# Sheet1.net
KiCad netlist of a schematic drawn in Altium Designer
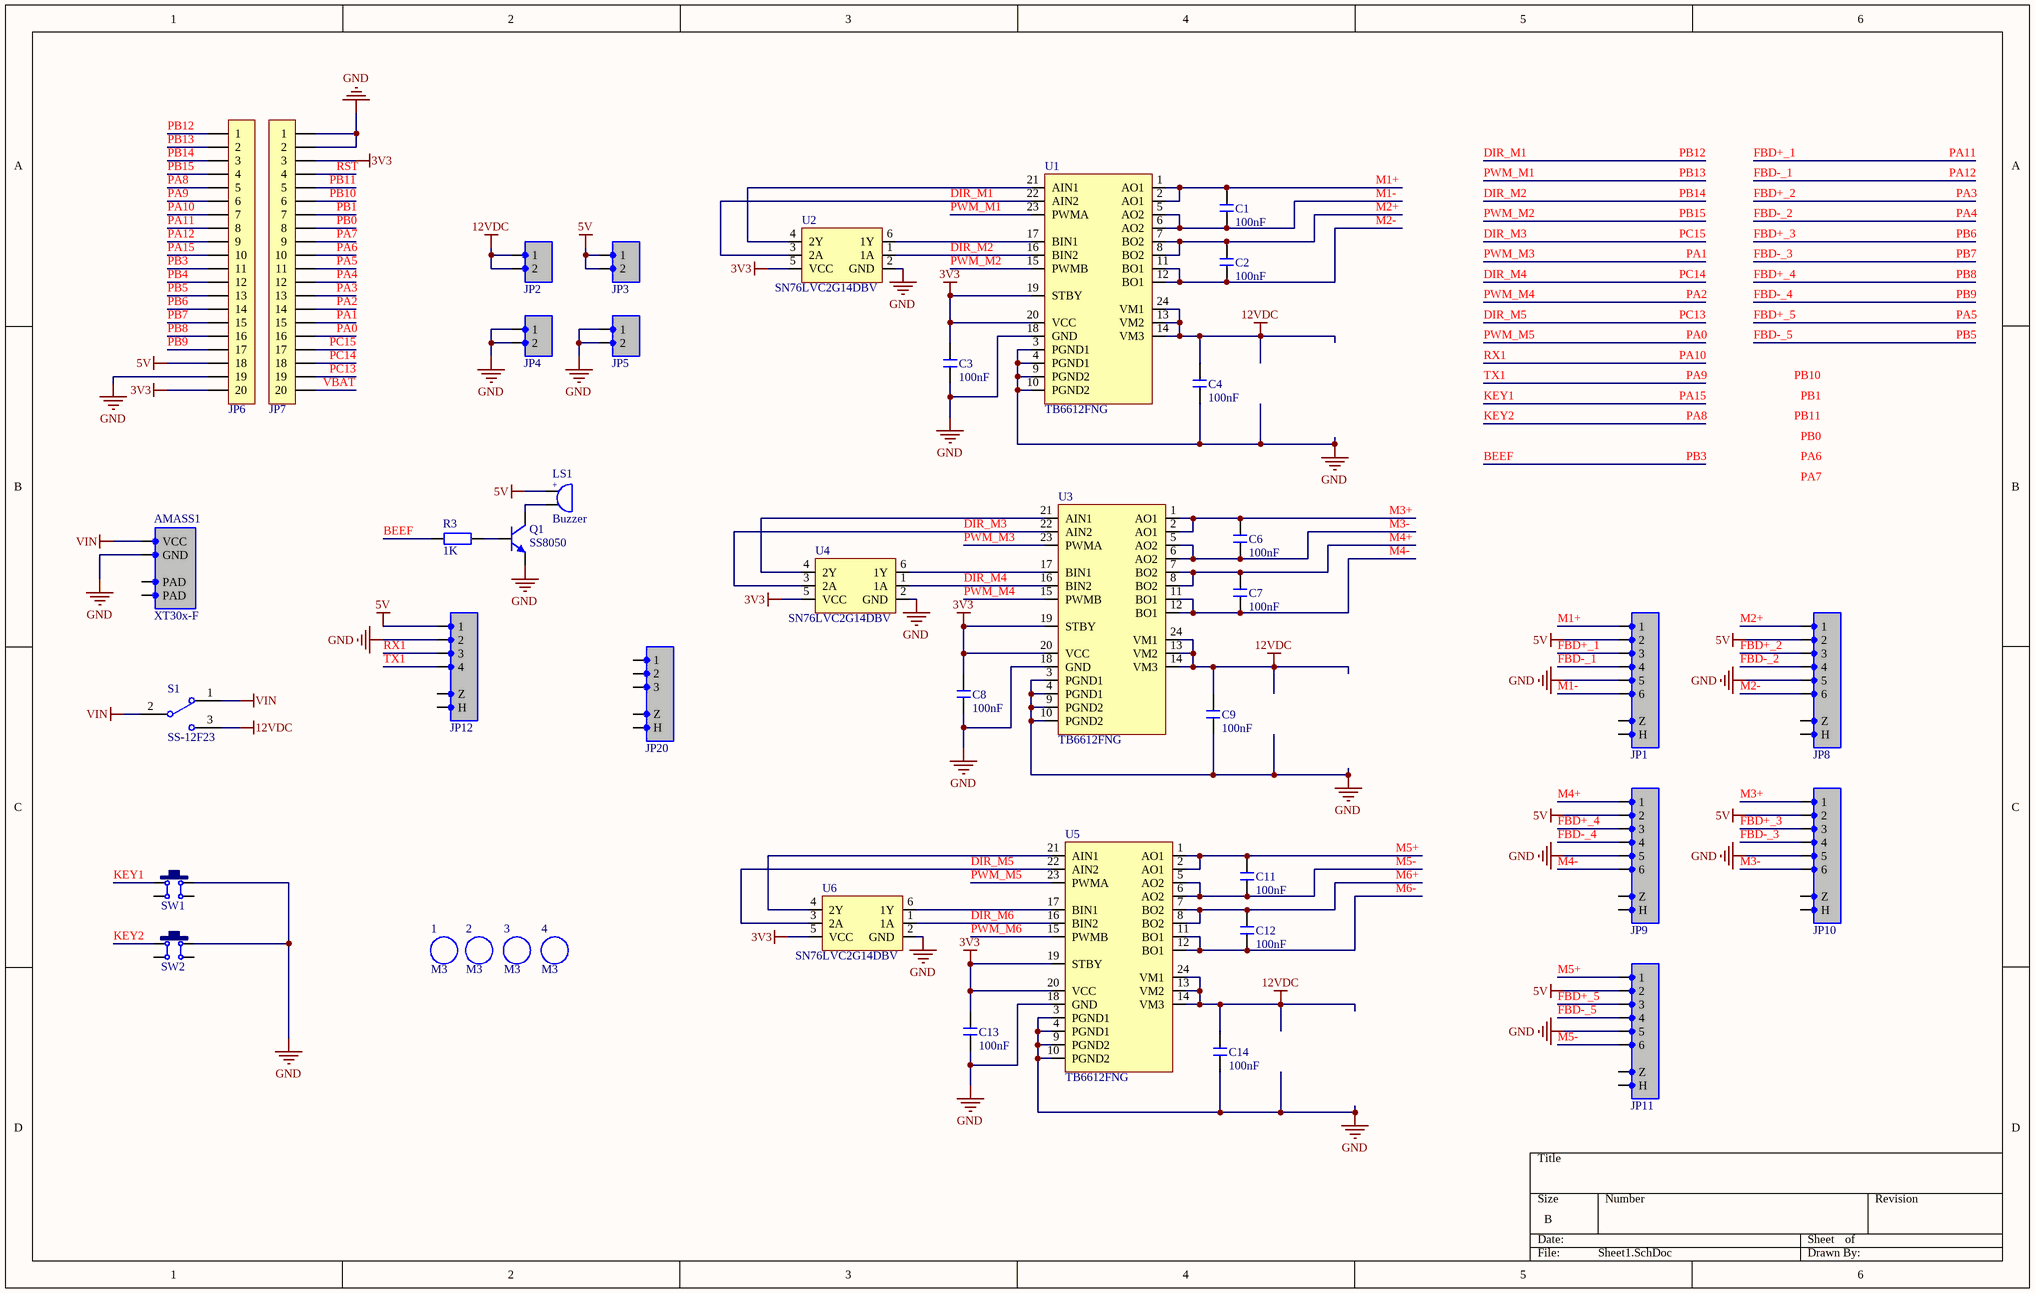
[diagram p0: Sheet1.SchDoc]

(export (version "E")
  (design (tool "Eeschema 10.0.6"))
  (components
    (comp (ref "1")
      (value "M3")
      (footprint "M3 125X200")
      (description "铜柱孔")
      (fields (field (name "版权归属") "源创客"))
      (libsource (lib "13.1-未分类器件") (part "M3"))
    )
    (comp (ref "2")
      (value "M3")
      (footprint "M3 125X200")
      (description "铜柱孔")
      (fields (field (name "版权归属") "源创客"))
      (libsource (lib "13.1-未分类器件") (part "M3"))
    )
    (comp (ref "3")
      (value "M3")
      (footprint "M3 125X200")
      (description "铜柱孔")
      (fields (field (name "版权归属") "源创客"))
      (libsource (lib "13.1-未分类器件") (part "M3"))
    )
    (comp (ref "4")
      (value "M3")
      (footprint "M3 125X200")
      (description "铜柱孔")
      (fields (field (name "版权归属") "源创客"))
      (libsource (lib "13.1-未分类器件") (part "M3"))
    )
    (comp (ref "AMASS1")
      (value "XT30x-F")
      (footprint "XT30U-M")
      (description "Amass防打火电源接口，XT30系列")
      (libsource (lib "SCHLib") (part "XT30"))
    )
    (comp (ref "C1")
      (value "100nF")
      (footprint "C 0603_L")
      (description "无极性贴片电容")
      (fields (field (name "版权归属") "源创客"))
      (libsource (lib "3.2-电容") (part "C"))
    )
    (comp (ref "C2")
      (value "100nF")
      (footprint "C 0603_L")
      (description "无极性贴片电容")
      (fields (field (name "版权归属") "源创客"))
      (libsource (lib "3.2-电容") (part "C"))
    )
    (comp (ref "C3")
      (value "100nF")
      (footprint "C 0603_L")
      (description "无极性贴片电容")
      (fields (field (name "版权归属") "源创客"))
      (libsource (lib "3.2-电容") (part "C"))
    )
    (comp (ref "C4")
      (value "100nF")
      (footprint "C 1206_L")
      (description "无极性贴片电容")
      (fields (field (name "版权归属") "源创客"))
      (libsource (lib "3.2-电容") (part "C"))
    )
    (comp (ref "C6")
      (value "100nF")
      (footprint "C 0603_L")
      (description "无极性贴片电容")
      (fields (field (name "版权归属") "源创客"))
      (libsource (lib "3.2-电容") (part "C"))
    )
    (comp (ref "C7")
      (value "100nF")
      (footprint "C 0603_L")
      (description "无极性贴片电容")
      (fields (field (name "版权归属") "源创客"))
      (libsource (lib "3.2-电容") (part "C"))
    )
    (comp (ref "C8")
      (value "100nF")
      (footprint "C 0603_L")
      (description "无极性贴片电容")
      (fields (field (name "版权归属") "源创客"))
      (libsource (lib "3.2-电容") (part "C"))
    )
    (comp (ref "C9")
      (value "100nF")
      (footprint "C 1206_L")
      (description "无极性贴片电容")
      (fields (field (name "版权归属") "源创客"))
      (libsource (lib "3.2-电容") (part "C"))
    )
    (comp (ref "C11")
      (value "100nF")
      (footprint "C 0603_L")
      (description "无极性贴片电容")
      (fields (field (name "版权归属") "源创客"))
      (libsource (lib "3.2-电容") (part "C"))
    )
    (comp (ref "C12")
      (value "100nF")
      (footprint "C 0603_L")
      (description "无极性贴片电容")
      (fields (field (name "版权归属") "源创客"))
      (libsource (lib "3.2-电容") (part "C"))
    )
    (comp (ref "C13")
      (value "100nF")
      (footprint "C 0603_L")
      (description "无极性贴片电容")
      (fields (field (name "版权归属") "源创客"))
      (libsource (lib "3.2-电容") (part "C"))
    )
    (comp (ref "C14")
      (value "100nF")
      (footprint "C 1206_L")
      (description "无极性贴片电容")
      (fields (field (name "版权归属") "源创客"))
      (libsource (lib "3.2-电容") (part "C"))
    )
    (comp (ref "JP1")
      (value "HDR-1X6")
      (footprint "XH2.54-WI-6P")
      (description "6P接插件")
      (fields (field (name "版权归属") "源创客"))
      (libsource (lib "14.6-接插件-脚距2.54") (part "Header 6"))
    )
    (comp (ref "JP2")
      (value "HDR-1X2")
      (footprint "HDR2.54-LI-2P")
      (description "2P接插件")
      (fields (field (name "版权归属") "源创客"))
      (libsource (lib "14.6-接插件-脚距2.54") (part "Header 2"))
    )
    (comp (ref "JP3")
      (value "HDR-1X2")
      (footprint "HDR2.54-LI-2P")
      (description "2P接插件")
      (fields (field (name "版权归属") "源创客"))
      (libsource (lib "14.6-接插件-脚距2.54") (part "Header 2"))
    )
    (comp (ref "JP4")
      (value "HDR-1X2")
      (footprint "HDR2.54-LI-2P")
      (description "2P接插件")
      (fields (field (name "版权归属") "源创客"))
      (libsource (lib "14.6-接插件-脚距2.54") (part "Header 2"))
    )
    (comp (ref "JP5")
      (value "HDR-1X2")
      (footprint "HDR2.54-LI-2P")
      (description "2P接插件")
      (fields (field (name "版权归属") "源创客"))
      (libsource (lib "14.6-接插件-脚距2.54") (part "Header 2"))
    )
    (comp (ref "JP6")
      (value "HDR-1X20")
      (footprint "HDR2.54-LI-20P")
      (description "20P接插件")
      (fields (field (name "版权归属") "源创客"))
      (libsource (lib "14.6-接插件-脚距2.54") (part "Header 20"))
    )
    (comp (ref "JP7")
      (value "HDR-1X20")
      (footprint "HDR2.54-LI-20P")
      (description "20P接插件")
      (fields (field (name "版权归属") "源创客"))
      (libsource (lib "") (part "Header 20_1"))
    )
    (comp (ref "JP8")
      (value "HDR-1X6")
      (footprint "XH2.54-WI-6P")
      (description "6P接插件")
      (fields (field (name "版权归属") "源创客"))
      (libsource (lib "14.6-接插件-脚距2.54") (part "Header 6"))
    )
    (comp (ref "JP9")
      (value "HDR-1X6")
      (footprint "XH2.54-WI-6P")
      (description "6P接插件")
      (fields (field (name "版权归属") "源创客"))
      (libsource (lib "14.6-接插件-脚距2.54") (part "Header 6"))
    )
    (comp (ref "JP10")
      (value "HDR-1X6")
      (footprint "XH2.54-WI-6P")
      (description "6P接插件")
      (fields (field (name "版权归属") "源创客"))
      (libsource (lib "14.6-接插件-脚距2.54") (part "Header 6"))
    )
    (comp (ref "JP11")
      (value "HDR-1X6")
      (footprint "XH2.54-WI-6P")
      (description "6P接插件")
      (fields (field (name "版权归属") "源创客"))
      (libsource (lib "14.6-接插件-脚距2.54") (part "Header 6"))
    )
    (comp (ref "JP12")
      (value "HDR-1X4")
      (footprint "HDR2.54-LI-4P")
      (description "4P接插件")
      (fields (field (name "版权归属") "源创客"))
      (libsource (lib "14.6-接插件-脚距2.54") (part "Header 4"))
    )
    (comp (ref "JP20")
      (value "HDR-1X3")
      (footprint "HDR2.54-M-LI-3P")
      (description "3P接插件")
      (fields (field (name "版权归属") "源创客"))
      (libsource (lib "14.6-接插件-脚距2.54") (part "Header 3"))
    )
    (comp (ref "LS1")
      (value "Buzzer")
      (footprint "BUZZER_1260_I")
      (description "蜂鸣器")
      (fields (field (name "版权归属") "源创客"))
      (libsource (lib "13.1-未分类器件") (part "Buzzer"))
    )
    (comp (ref "Q1")
      (value "SS8050")
      (footprint "SOT23-3N")
      (description "高频放大-NPN型")
      (fields (field (name "版权归属") "源创客"))
      (libsource (lib "5.1-三极管") (part "8050-SMD"))
    )
    (comp (ref "R3")
      (value "1K")
      (footprint "R 0603_L")
      (description "贴片电阻")
      (fields (field (name "版权归属") "源创客"))
      (libsource (lib "3.1-电阻") (part "R"))
    )
    (comp (ref "S1")
      (value "SS-12F23")
      (footprint "SS-12D10")
      (description "1路拨动开关")
      (fields (field (name "版权归属") "源创客"))
      (libsource (lib "6.2-开关") (part "SSW-1P"))
    )
    (comp (ref "SW1")
      (value "6x6x5")
      (footprint "TSW SMD-6*6*4.3")
      (description "贴片6x6轻触开关")
      (fields (field (name "版权归属") "源创客"))
      (libsource (lib "6.1-按键") (part "TSW SMD-6x6"))
    )
    (comp (ref "SW2")
      (value "6x6x5")
      (footprint "TSW SMD-6*6*4.3")
      (description "贴片6x6轻触开关")
      (fields (field (name "版权归属") "源创客"))
      (libsource (lib "6.1-按键") (part "TSW SMD-6x6"))
    )
    (comp (ref "U1")
      (value "TB6612FNG")
      (footprint "SSOP24_N")
      (libsource (lib "Schlib1") (part "Component_1"))
    )
    (comp (ref "U2")
      (value "SN76LVC2G14DBV")
      (footprint "SOT23-6N")
      (libsource (lib "Schlib1") (part "SN76LVC2G14DBV"))
    )
    (comp (ref "U3")
      (value "TB6612FNG")
      (footprint "SSOP24_N")
      (libsource (lib "Schlib1") (part "Component_1"))
    )
    (comp (ref "U4")
      (value "SN76LVC2G14DBV")
      (footprint "SOT23-6N")
      (libsource (lib "Schlib1") (part "SN76LVC2G14DBV"))
    )
    (comp (ref "U5")
      (value "TB6612FNG")
      (footprint "SSOP24_N")
      (libsource (lib "Schlib1") (part "Component_1"))
    )
    (comp (ref "U6")
      (value "SN76LVC2G14DBV")
      (footprint "SOT23-6N")
      (libsource (lib "Schlib1") (part "SN76LVC2G14DBV"))
    )
  )
  (nets
    (net (code "1") (name "/BEEF") (class "Default")
      (node (ref "JP6") (pin "11") (pinfunction "11_11") (pintype "passive"))
      (node (ref "R3") (pin "2") (pinfunction "2_2") (pintype "passive"))
    )
    (net (code "2") (name "/DIR_M1") (class "Default")
      (node (ref "JP6") (pin "1") (pinfunction "1_1") (pintype "passive"))
      (node (ref "U1") (pin "22") (pinfunction "AIN2_22") (pintype "passive"))
      (node (ref "U2") (pin "3") (pinfunction "2A_3") (pintype "passive"))
    )
    (net (code "3") (name "/DIR_M2") (class "Default")
      (node (ref "JP6") (pin "3") (pinfunction "3_3") (pintype "passive"))
      (node (ref "U1") (pin "16") (pinfunction "BIN2_16") (pintype "passive"))
      (node (ref "U2") (pin "1") (pinfunction "1A_1") (pintype "passive"))
    )
    (net (code "4") (name "/DIR_M3") (class "Default")
      (node (ref "JP7") (pin "17") (pinfunction "17_17") (pintype "passive"))
      (node (ref "U3") (pin "22") (pinfunction "AIN2_22") (pintype "passive"))
      (node (ref "U4") (pin "3") (pinfunction "2A_3") (pintype "passive"))
    )
    (net (code "5") (name "/DIR_M4") (class "Default")
      (node (ref "JP7") (pin "18") (pinfunction "18_18") (pintype "passive"))
      (node (ref "U3") (pin "16") (pinfunction "BIN2_16") (pintype "passive"))
      (node (ref "U4") (pin "1") (pinfunction "1A_1") (pintype "passive"))
    )
    (net (code "6") (name "/DIR_M5") (class "Default")
      (node (ref "JP7") (pin "19") (pinfunction "19_19") (pintype "passive"))
      (node (ref "U5") (pin "22") (pinfunction "AIN2_22") (pintype "passive"))
      (node (ref "U6") (pin "3") (pinfunction "2A_3") (pintype "passive"))
    )
    (net (code "7") (name "/DIR_M6") (class "Default")
      (node (ref "U5") (pin "16") (pinfunction "BIN2_16") (pintype "passive"))
      (node (ref "U6") (pin "1") (pinfunction "1A_1") (pintype "passive"))
    )
    (net (code "8") (name "/FBD+_1") (class "Default")
      (node (ref "JP1") (pin "3") (pinfunction "3_3") (pintype "passive"))
      (node (ref "JP6") (pin "8") (pinfunction "8_8") (pintype "passive"))
    )
    (net (code "9") (name "/FBD+_2") (class "Default")
      (node (ref "JP7") (pin "13") (pinfunction "13_13") (pintype "passive"))
      (node (ref "JP8") (pin "3") (pinfunction "3_3") (pintype "passive"))
    )
    (net (code "10") (name "/FBD+_3") (class "Default")
      (node (ref "JP10") (pin "3") (pinfunction "3_3") (pintype "passive"))
      (node (ref "JP6") (pin "14") (pinfunction "14_14") (pintype "passive"))
    )
    (net (code "11") (name "/FBD+_4") (class "Default")
      (node (ref "JP6") (pin "16") (pinfunction "16_16") (pintype "passive"))
      (node (ref "JP9") (pin "3") (pinfunction "3_3") (pintype "passive"))
    )
    (net (code "12") (name "/FBD+_5") (class "Default")
      (node (ref "JP11") (pin "3") (pinfunction "3_3") (pintype "passive"))
      (node (ref "JP7") (pin "11") (pinfunction "11_11") (pintype "passive"))
    )
    (net (code "13") (name "/FBD-_1") (class "Default")
      (node (ref "JP1") (pin "4") (pinfunction "4_4") (pintype "passive"))
      (node (ref "JP6") (pin "9") (pinfunction "9_9") (pintype "passive"))
    )
    (net (code "14") (name "/FBD-_2") (class "Default")
      (node (ref "JP7") (pin "12") (pinfunction "12_12") (pintype "passive"))
      (node (ref "JP8") (pin "4") (pinfunction "4_4") (pintype "passive"))
    )
    (net (code "15") (name "/FBD-_3") (class "Default")
      (node (ref "JP10") (pin "4") (pinfunction "4_4") (pintype "passive"))
      (node (ref "JP6") (pin "15") (pinfunction "15_15") (pintype "passive"))
    )
    (net (code "16") (name "/FBD-_4") (class "Default")
      (node (ref "JP6") (pin "17") (pinfunction "17_17") (pintype "passive"))
      (node (ref "JP9") (pin "4") (pinfunction "4_4") (pintype "passive"))
    )
    (net (code "17") (name "/FBD-_5") (class "Default")
      (node (ref "JP11") (pin "4") (pinfunction "4_4") (pintype "passive"))
      (node (ref "JP6") (pin "13") (pinfunction "13_13") (pintype "passive"))
    )
    (net (code "18") (name "/KEY1") (class "Default")
      (node (ref "JP6") (pin "10") (pinfunction "10_10") (pintype "passive"))
      (node (ref "SW1") (pin "1") (pinfunction "1_1") (pintype "passive"))
    )
    (net (code "19") (name "/KEY2") (class "Default")
      (node (ref "JP6") (pin "5") (pinfunction "5_5") (pintype "passive"))
      (node (ref "SW2") (pin "1") (pinfunction "1_1") (pintype "passive"))
    )
    (net (code "20") (name "/M1+") (class "Default")
      (node (ref "C1") (pin "2") (pinfunction "2_2") (pintype "passive"))
      (node (ref "JP1") (pin "1") (pinfunction "1_1") (pintype "passive"))
      (node (ref "U1") (pin "1") (pinfunction "AO1_1") (pintype "passive"))
      (node (ref "U1") (pin "2") (pinfunction "AO1_2") (pintype "passive"))
    )
    (net (code "21") (name "/M1-") (class "Default")
      (node (ref "C1") (pin "1") (pinfunction "1_1") (pintype "passive"))
      (node (ref "JP1") (pin "6") (pinfunction "6_6") (pintype "passive"))
      (node (ref "U1") (pin "5") (pinfunction "AO2_5") (pintype "passive"))
      (node (ref "U1") (pin "6") (pinfunction "AO2_6") (pintype "passive"))
    )
    (net (code "22") (name "/M2+") (class "Default")
      (node (ref "C2") (pin "2") (pinfunction "2_2") (pintype "passive"))
      (node (ref "JP8") (pin "1") (pinfunction "1_1") (pintype "passive"))
      (node (ref "U1") (pin "7") (pinfunction "BO2_7") (pintype "passive"))
      (node (ref "U1") (pin "8") (pinfunction "BO2_8") (pintype "passive"))
    )
    (net (code "23") (name "/M2-") (class "Default")
      (node (ref "C2") (pin "1") (pinfunction "1_1") (pintype "passive"))
      (node (ref "JP8") (pin "6") (pinfunction "6_6") (pintype "passive"))
      (node (ref "U1") (pin "11") (pinfunction "BO1_11") (pintype "passive"))
      (node (ref "U1") (pin "12") (pinfunction "BO1_12") (pintype "passive"))
    )
    (net (code "24") (name "/M3+") (class "Default")
      (node (ref "C6") (pin "2") (pinfunction "2_2") (pintype "passive"))
      (node (ref "JP10") (pin "1") (pinfunction "1_1") (pintype "passive"))
      (node (ref "U3") (pin "1") (pinfunction "AO1_1") (pintype "passive"))
      (node (ref "U3") (pin "2") (pinfunction "AO1_2") (pintype "passive"))
    )
    (net (code "25") (name "/M3-") (class "Default")
      (node (ref "C6") (pin "1") (pinfunction "1_1") (pintype "passive"))
      (node (ref "JP10") (pin "6") (pinfunction "6_6") (pintype "passive"))
      (node (ref "U3") (pin "5") (pinfunction "AO2_5") (pintype "passive"))
      (node (ref "U3") (pin "6") (pinfunction "AO2_6") (pintype "passive"))
    )
    (net (code "26") (name "/M4+") (class "Default")
      (node (ref "C7") (pin "2") (pinfunction "2_2") (pintype "passive"))
      (node (ref "JP9") (pin "1") (pinfunction "1_1") (pintype "passive"))
      (node (ref "U3") (pin "7") (pinfunction "BO2_7") (pintype "passive"))
      (node (ref "U3") (pin "8") (pinfunction "BO2_8") (pintype "passive"))
    )
    (net (code "27") (name "/M4-") (class "Default")
      (node (ref "C7") (pin "1") (pinfunction "1_1") (pintype "passive"))
      (node (ref "JP9") (pin "6") (pinfunction "6_6") (pintype "passive"))
      (node (ref "U3") (pin "11") (pinfunction "BO1_11") (pintype "passive"))
      (node (ref "U3") (pin "12") (pinfunction "BO1_12") (pintype "passive"))
    )
    (net (code "28") (name "/M5+") (class "Default")
      (node (ref "C11") (pin "2") (pinfunction "2_2") (pintype "passive"))
      (node (ref "JP11") (pin "1") (pinfunction "1_1") (pintype "passive"))
      (node (ref "U5") (pin "1") (pinfunction "AO1_1") (pintype "passive"))
      (node (ref "U5") (pin "2") (pinfunction "AO1_2") (pintype "passive"))
    )
    (net (code "29") (name "/M5-") (class "Default")
      (node (ref "C11") (pin "1") (pinfunction "1_1") (pintype "passive"))
      (node (ref "JP11") (pin "6") (pinfunction "6_6") (pintype "passive"))
      (node (ref "U5") (pin "5") (pinfunction "AO2_5") (pintype "passive"))
      (node (ref "U5") (pin "6") (pinfunction "AO2_6") (pintype "passive"))
    )
    (net (code "30") (name "/M6+") (class "Default")
      (node (ref "C12") (pin "2") (pinfunction "2_2") (pintype "passive"))
      (node (ref "U5") (pin "7") (pinfunction "BO2_7") (pintype "passive"))
      (node (ref "U5") (pin "8") (pinfunction "BO2_8") (pintype "passive"))
    )
    (net (code "31") (name "/M6-") (class "Default")
      (node (ref "C12") (pin "1") (pinfunction "1_1") (pintype "passive"))
      (node (ref "U5") (pin "11") (pinfunction "BO1_11") (pintype "passive"))
      (node (ref "U5") (pin "12") (pinfunction "BO1_12") (pintype "passive"))
    )
    (net (code "32") (name "/PA0") (class "Default")
      (node (ref "JP7") (pin "16") (pinfunction "16_16") (pintype "passive"))
      (node (ref "U5") (pin "23") (pinfunction "PWMA_23") (pintype "passive"))
    )
    (net (code "33") (name "/PA1") (class "Default")
      (node (ref "JP7") (pin "15") (pinfunction "15_15") (pintype "passive"))
      (node (ref "U3") (pin "23") (pinfunction "PWMA_23") (pintype "passive"))
    )
    (net (code "34") (name "/PA2") (class "Default")
      (node (ref "JP7") (pin "14") (pinfunction "14_14") (pintype "passive"))
      (node (ref "U3") (pin "15") (pinfunction "PWMB_15") (pintype "passive"))
    )
    (net (code "35") (name "/PA6") (class "Default")
      (node (ref "JP7") (pin "10") (pinfunction "10_10") (pintype "passive"))
    )
    (net (code "36") (name "/PA7") (class "Default")
      (node (ref "JP7") (pin "9") (pinfunction "9_9") (pintype "passive"))
    )
    (net (code "37") (name "/PA9") (class "Default")
      (node (ref "JP12") (pin "4") (pinfunction "4_4") (pintype "passive"))
      (node (ref "JP6") (pin "6") (pinfunction "6_6") (pintype "passive"))
    )
    (net (code "38") (name "/PA10") (class "Default")
      (node (ref "JP12") (pin "3") (pinfunction "3_3") (pintype "passive"))
      (node (ref "JP6") (pin "7") (pinfunction "7_7") (pintype "passive"))
    )
    (net (code "39") (name "/PB0") (class "Default")
      (node (ref "JP7") (pin "8") (pinfunction "8_8") (pintype "passive"))
    )
    (net (code "40") (name "/PB1") (class "Default")
      (node (ref "JP7") (pin "7") (pinfunction "7_7") (pintype "passive"))
    )
    (net (code "41") (name "/PB4") (class "Default")
      (node (ref "JP6") (pin "12") (pinfunction "12_12") (pintype "passive"))
    )
    (net (code "42") (name "/PB10") (class "Default")
      (node (ref "JP7") (pin "6") (pinfunction "6_6") (pintype "passive"))
    )
    (net (code "43") (name "/PB11") (class "Default")
      (node (ref "JP7") (pin "5") (pinfunction "5_5") (pintype "passive"))
    )
    (net (code "44") (name "/PB13") (class "Default")
      (node (ref "JP6") (pin "2") (pinfunction "2_2") (pintype "passive"))
      (node (ref "U1") (pin "23") (pinfunction "PWMA_23") (pintype "passive"))
    )
    (net (code "45") (name "/PB15") (class "Default")
      (node (ref "JP6") (pin "4") (pinfunction "4_4") (pintype "passive"))
      (node (ref "U1") (pin "15") (pinfunction "PWMB_15") (pintype "passive"))
    )
    (net (code "46") (name "/PWM_M6") (class "Default")
      (node (ref "U5") (pin "15") (pinfunction "PWMB_15") (pintype "passive"))
    )
    (net (code "47") (name "/RST") (class "Default")
      (node (ref "JP7") (pin "4") (pinfunction "4_4") (pintype "passive"))
    )
    (net (code "48") (name "/VBAT") (class "Default")
      (node (ref "JP7") (pin "20") (pinfunction "20_20") (pintype "passive"))
    )
    (net (code "49") (name "3V3") (class "Default")
      (node (ref "C13") (pin "2") (pinfunction "2_2") (pintype "passive"))
      (node (ref "C3") (pin "2") (pinfunction "2_2") (pintype "passive"))
      (node (ref "C8") (pin "2") (pinfunction "2_2") (pintype "passive"))
      (node (ref "JP6") (pin "20") (pinfunction "20_20") (pintype "passive"))
      (node (ref "JP7") (pin "3") (pinfunction "3_3") (pintype "passive"))
      (node (ref "U1") (pin "19") (pinfunction "STBY_19") (pintype "passive"))
      (node (ref "U1") (pin "20") (pinfunction "VCC_20") (pintype "passive"))
      (node (ref "U2") (pin "5") (pinfunction "VCC_5") (pintype "passive"))
      (node (ref "U3") (pin "19") (pinfunction "STBY_19") (pintype "passive"))
      (node (ref "U3") (pin "20") (pinfunction "VCC_20") (pintype "passive"))
      (node (ref "U4") (pin "5") (pinfunction "VCC_5") (pintype "passive"))
      (node (ref "U5") (pin "19") (pinfunction "STBY_19") (pintype "passive"))
      (node (ref "U5") (pin "20") (pinfunction "VCC_20") (pintype "passive"))
      (node (ref "U6") (pin "5") (pinfunction "VCC_5") (pintype "passive"))
    )
    (net (code "50") (name "5V") (class "Default")
      (node (ref "JP1") (pin "2") (pinfunction "2_2") (pintype "passive"))
      (node (ref "JP10") (pin "2") (pinfunction "2_2") (pintype "passive"))
      (node (ref "JP11") (pin "2") (pinfunction "2_2") (pintype "passive"))
      (node (ref "JP12") (pin "1") (pinfunction "1_1") (pintype "passive"))
      (node (ref "JP3") (pin "1") (pinfunction "1_1") (pintype "passive"))
      (node (ref "JP3") (pin "2") (pinfunction "2_2") (pintype "passive"))
      (node (ref "JP6") (pin "18") (pinfunction "18_18") (pintype "passive"))
      (node (ref "JP8") (pin "2") (pinfunction "2_2") (pintype "passive"))
      (node (ref "JP9") (pin "2") (pinfunction "2_2") (pintype "passive"))
      (node (ref "LS1") (pin "1") (pinfunction "1_1") (pintype "passive"))
    )
    (net (code "51") (name "12VDC") (class "Default")
      (node (ref "C14") (pin "2") (pinfunction "2_2") (pintype "passive"))
      (node (ref "C4") (pin "2") (pinfunction "2_2") (pintype "passive"))
      (node (ref "C9") (pin "2") (pinfunction "2_2") (pintype "passive"))
      (node (ref "JP2") (pin "1") (pinfunction "1_1") (pintype "passive"))
      (node (ref "JP2") (pin "2") (pinfunction "2_2") (pintype "passive"))
      (node (ref "S1") (pin "3") (pinfunction "3_3") (pintype "passive"))
      (node (ref "U1") (pin "13") (pinfunction "VM2_13") (pintype "passive"))
      (node (ref "U1") (pin "14") (pinfunction "VM3_14") (pintype "passive"))
      (node (ref "U1") (pin "24") (pinfunction "VM1_24") (pintype "passive"))
      (node (ref "U3") (pin "13") (pinfunction "VM2_13") (pintype "passive"))
      (node (ref "U3") (pin "14") (pinfunction "VM3_14") (pintype "passive"))
      (node (ref "U3") (pin "24") (pinfunction "VM1_24") (pintype "passive"))
      (node (ref "U5") (pin "13") (pinfunction "VM2_13") (pintype "passive"))
      (node (ref "U5") (pin "14") (pinfunction "VM3_14") (pintype "passive"))
      (node (ref "U5") (pin "24") (pinfunction "VM1_24") (pintype "passive"))
    )
    (net (code "52") (name "GND") (class "Default")
      (node (ref "AMASS1") (pin "2") (pinfunction "GND_2") (pintype "passive"))
      (node (ref "C13") (pin "1") (pinfunction "1_1") (pintype "passive"))
      (node (ref "C14") (pin "1") (pinfunction "1_1") (pintype "passive"))
      (node (ref "C3") (pin "1") (pinfunction "1_1") (pintype "passive"))
      (node (ref "C4") (pin "1") (pinfunction "1_1") (pintype "passive"))
      (node (ref "C8") (pin "1") (pinfunction "1_1") (pintype "passive"))
      (node (ref "C9") (pin "1") (pinfunction "1_1") (pintype "passive"))
      (node (ref "JP1") (pin "5") (pinfunction "5_5") (pintype "passive"))
      (node (ref "JP10") (pin "5") (pinfunction "5_5") (pintype "passive"))
      (node (ref "JP11") (pin "5") (pinfunction "5_5") (pintype "passive"))
      (node (ref "JP12") (pin "2") (pinfunction "2_2") (pintype "passive"))
      (node (ref "JP4") (pin "1") (pinfunction "1_1") (pintype "passive"))
      (node (ref "JP4") (pin "2") (pinfunction "2_2") (pintype "passive"))
      (node (ref "JP5") (pin "1") (pinfunction "1_1") (pintype "passive"))
      (node (ref "JP5") (pin "2") (pinfunction "2_2") (pintype "passive"))
      (node (ref "JP6") (pin "19") (pinfunction "19_19") (pintype "passive"))
      (node (ref "JP7") (pin "1") (pinfunction "1_1") (pintype "passive"))
      (node (ref "JP7") (pin "2") (pinfunction "2_2") (pintype "passive"))
      (node (ref "JP8") (pin "5") (pinfunction "5_5") (pintype "passive"))
      (node (ref "JP9") (pin "5") (pinfunction "5_5") (pintype "passive"))
      (node (ref "Q1") (pin "2") (pinfunction "E_2") (pintype "passive"))
      (node (ref "SW1") (pin "2") (pinfunction "2_2") (pintype "passive"))
      (node (ref "SW2") (pin "2") (pinfunction "2_2") (pintype "passive"))
      (node (ref "U1") (pin "10") (pinfunction "PGND2_10") (pintype "passive"))
      (node (ref "U1") (pin "18") (pinfunction "GND_18") (pintype "passive"))
      (node (ref "U1") (pin "3") (pinfunction "PGND1_3") (pintype "passive"))
      (node (ref "U1") (pin "4") (pinfunction "PGND1_4") (pintype "passive"))
      (node (ref "U1") (pin "9") (pinfunction "PGND2_9") (pintype "passive"))
      (node (ref "U2") (pin "2") (pinfunction "GND_2") (pintype "passive"))
      (node (ref "U3") (pin "10") (pinfunction "PGND2_10") (pintype "passive"))
      (node (ref "U3") (pin "18") (pinfunction "GND_18") (pintype "passive"))
      (node (ref "U3") (pin "3") (pinfunction "PGND1_3") (pintype "passive"))
      (node (ref "U3") (pin "4") (pinfunction "PGND1_4") (pintype "passive"))
      (node (ref "U3") (pin "9") (pinfunction "PGND2_9") (pintype "passive"))
      (node (ref "U4") (pin "2") (pinfunction "GND_2") (pintype "passive"))
      (node (ref "U5") (pin "10") (pinfunction "PGND2_10") (pintype "passive"))
      (node (ref "U5") (pin "18") (pinfunction "GND_18") (pintype "passive"))
      (node (ref "U5") (pin "3") (pinfunction "PGND1_3") (pintype "passive"))
      (node (ref "U5") (pin "4") (pinfunction "PGND1_4") (pintype "passive"))
      (node (ref "U5") (pin "9") (pinfunction "PGND2_9") (pintype "passive"))
      (node (ref "U6") (pin "2") (pinfunction "GND_2") (pintype "passive"))
    )
    (net (code "53") (name "Net-(Q1-B)") (class "Default")
      (node (ref "Q1") (pin "1") (pinfunction "B_1") (pintype "passive"))
      (node (ref "R3") (pin "1") (pinfunction "1_1") (pintype "passive"))
    )
    (net (code "54") (name "Net-(Q1-C)") (class "Default")
      (node (ref "LS1") (pin "2") (pinfunction "2_2") (pintype "passive"))
      (node (ref "Q1") (pin "3") (pinfunction "C_3") (pintype "passive"))
    )
    (net (code "55") (name "Net-(U1-AIN1)") (class "Default")
      (node (ref "U1") (pin "21") (pinfunction "AIN1_21") (pintype "passive"))
      (node (ref "U2") (pin "4") (pinfunction "2Y_4") (pintype "passive"))
    )
    (net (code "56") (name "Net-(U1-BIN1)") (class "Default")
      (node (ref "U1") (pin "17") (pinfunction "BIN1_17") (pintype "passive"))
      (node (ref "U2") (pin "6") (pinfunction "1Y_6") (pintype "passive"))
    )
    (net (code "57") (name "Net-(U3-AIN1)") (class "Default")
      (node (ref "U3") (pin "21") (pinfunction "AIN1_21") (pintype "passive"))
      (node (ref "U4") (pin "4") (pinfunction "2Y_4") (pintype "passive"))
    )
    (net (code "58") (name "Net-(U3-BIN1)") (class "Default")
      (node (ref "U3") (pin "17") (pinfunction "BIN1_17") (pintype "passive"))
      (node (ref "U4") (pin "6") (pinfunction "1Y_6") (pintype "passive"))
    )
    (net (code "59") (name "Net-(U5-AIN1)") (class "Default")
      (node (ref "U5") (pin "21") (pinfunction "AIN1_21") (pintype "passive"))
      (node (ref "U6") (pin "4") (pinfunction "2Y_4") (pintype "passive"))
    )
    (net (code "60") (name "Net-(U5-BIN1)") (class "Default")
      (node (ref "U5") (pin "17") (pinfunction "BIN1_17") (pintype "passive"))
      (node (ref "U6") (pin "6") (pinfunction "1Y_6") (pintype "passive"))
    )
    (net (code "61") (name "VIN") (class "Default")
      (node (ref "AMASS1") (pin "1") (pinfunction "VCC_1") (pintype "passive"))
      (node (ref "S1") (pin "1") (pinfunction "1_1") (pintype "passive"))
      (node (ref "S1") (pin "2") (pinfunction "2_2") (pintype "passive"))
    )
    (net (code "62") (name "unconnected-(AMASS1-PAD-Pad0)") (class "Default")
      (node (ref "AMASS1") (pin "0") (pinfunction "PAD_0") (pintype "passive"))
    )
    (net (code "63") (name "unconnected-(AMASS1-PAD-Pad100)") (class "Default")
      (node (ref "AMASS1") (pin "100") (pinfunction "PAD_100") (pintype "passive"))
    )
    (net (code "64") (name "unconnected-(JP1-H-Pad100)") (class "Default")
      (node (ref "JP1") (pin "100") (pinfunction "H_100") (pintype "passive"))
    )
    (net (code "65") (name "unconnected-(JP1-Z-Pad0)") (class "Default")
      (node (ref "JP1") (pin "0") (pinfunction "Z_0") (pintype "passive"))
    )
    (net (code "66") (name "unconnected-(JP8-H-Pad100)") (class "Default")
      (node (ref "JP8") (pin "100") (pinfunction "H_100") (pintype "passive"))
    )
    (net (code "67") (name "unconnected-(JP8-Z-Pad0)") (class "Default")
      (node (ref "JP8") (pin "0") (pinfunction "Z_0") (pintype "passive"))
    )
    (net (code "68") (name "unconnected-(JP9-H-Pad100)") (class "Default")
      (node (ref "JP9") (pin "100") (pinfunction "H_100") (pintype "passive"))
    )
    (net (code "69") (name "unconnected-(JP9-Z-Pad0)") (class "Default")
      (node (ref "JP9") (pin "0") (pinfunction "Z_0") (pintype "passive"))
    )
    (net (code "70") (name "unconnected-(JP10-H-Pad100)") (class "Default")
      (node (ref "JP10") (pin "100") (pinfunction "H_100") (pintype "passive"))
    )
    (net (code "71") (name "unconnected-(JP10-Z-Pad0)") (class "Default")
      (node (ref "JP10") (pin "0") (pinfunction "Z_0") (pintype "passive"))
    )
    (net (code "72") (name "unconnected-(JP11-H-Pad100)") (class "Default")
      (node (ref "JP11") (pin "100") (pinfunction "H_100") (pintype "passive"))
    )
    (net (code "73") (name "unconnected-(JP11-Z-Pad0)") (class "Default")
      (node (ref "JP11") (pin "0") (pinfunction "Z_0") (pintype "passive"))
    )
    (net (code "74") (name "unconnected-(JP12-H-Pad100)") (class "Default")
      (node (ref "JP12") (pin "100") (pinfunction "H_100") (pintype "passive"))
    )
    (net (code "75") (name "unconnected-(JP12-Z-Pad0)") (class "Default")
      (node (ref "JP12") (pin "0") (pinfunction "Z_0") (pintype "passive"))
    )
    (net (code "76") (name "unconnected-(JP20-H-Pad100)") (class "Default")
      (node (ref "JP20") (pin "100") (pinfunction "H_100") (pintype "passive"))
    )
    (net (code "77") (name "unconnected-(JP20-Pad1)") (class "Default")
      (node (ref "JP20") (pin "1") (pinfunction "1_1") (pintype "passive"))
    )
    (net (code "78") (name "unconnected-(JP20-Pad2)") (class "Default")
      (node (ref "JP20") (pin "2") (pinfunction "2_2") (pintype "passive"))
    )
    (net (code "79") (name "unconnected-(JP20-Pad3)") (class "Default")
      (node (ref "JP20") (pin "3") (pinfunction "3_3") (pintype "passive"))
    )
    (net (code "80") (name "unconnected-(JP20-Z-Pad0)") (class "Default")
      (node (ref "JP20") (pin "0") (pinfunction "Z_0") (pintype "passive"))
    )
    (net (code "81") (name "unconnected-(SW1-Pad3)") (class "Default")
      (node (ref "SW1") (pin "3") (pinfunction "3_3") (pintype "passive"))
    )
    (net (code "82") (name "unconnected-(SW1-Pad4)") (class "Default")
      (node (ref "SW1") (pin "4") (pinfunction "4_4") (pintype "passive"))
    )
    (net (code "83") (name "unconnected-(SW2-Pad3)") (class "Default")
      (node (ref "SW2") (pin "3") (pinfunction "3_3") (pintype "passive"))
    )
    (net (code "84") (name "unconnected-(SW2-Pad4)") (class "Default")
      (node (ref "SW2") (pin "4") (pinfunction "4_4") (pintype "passive"))
    )
  )
)
